# Adafruit_LPS35HW.net
KiCad netlist of a schematic drawn in EAGLE
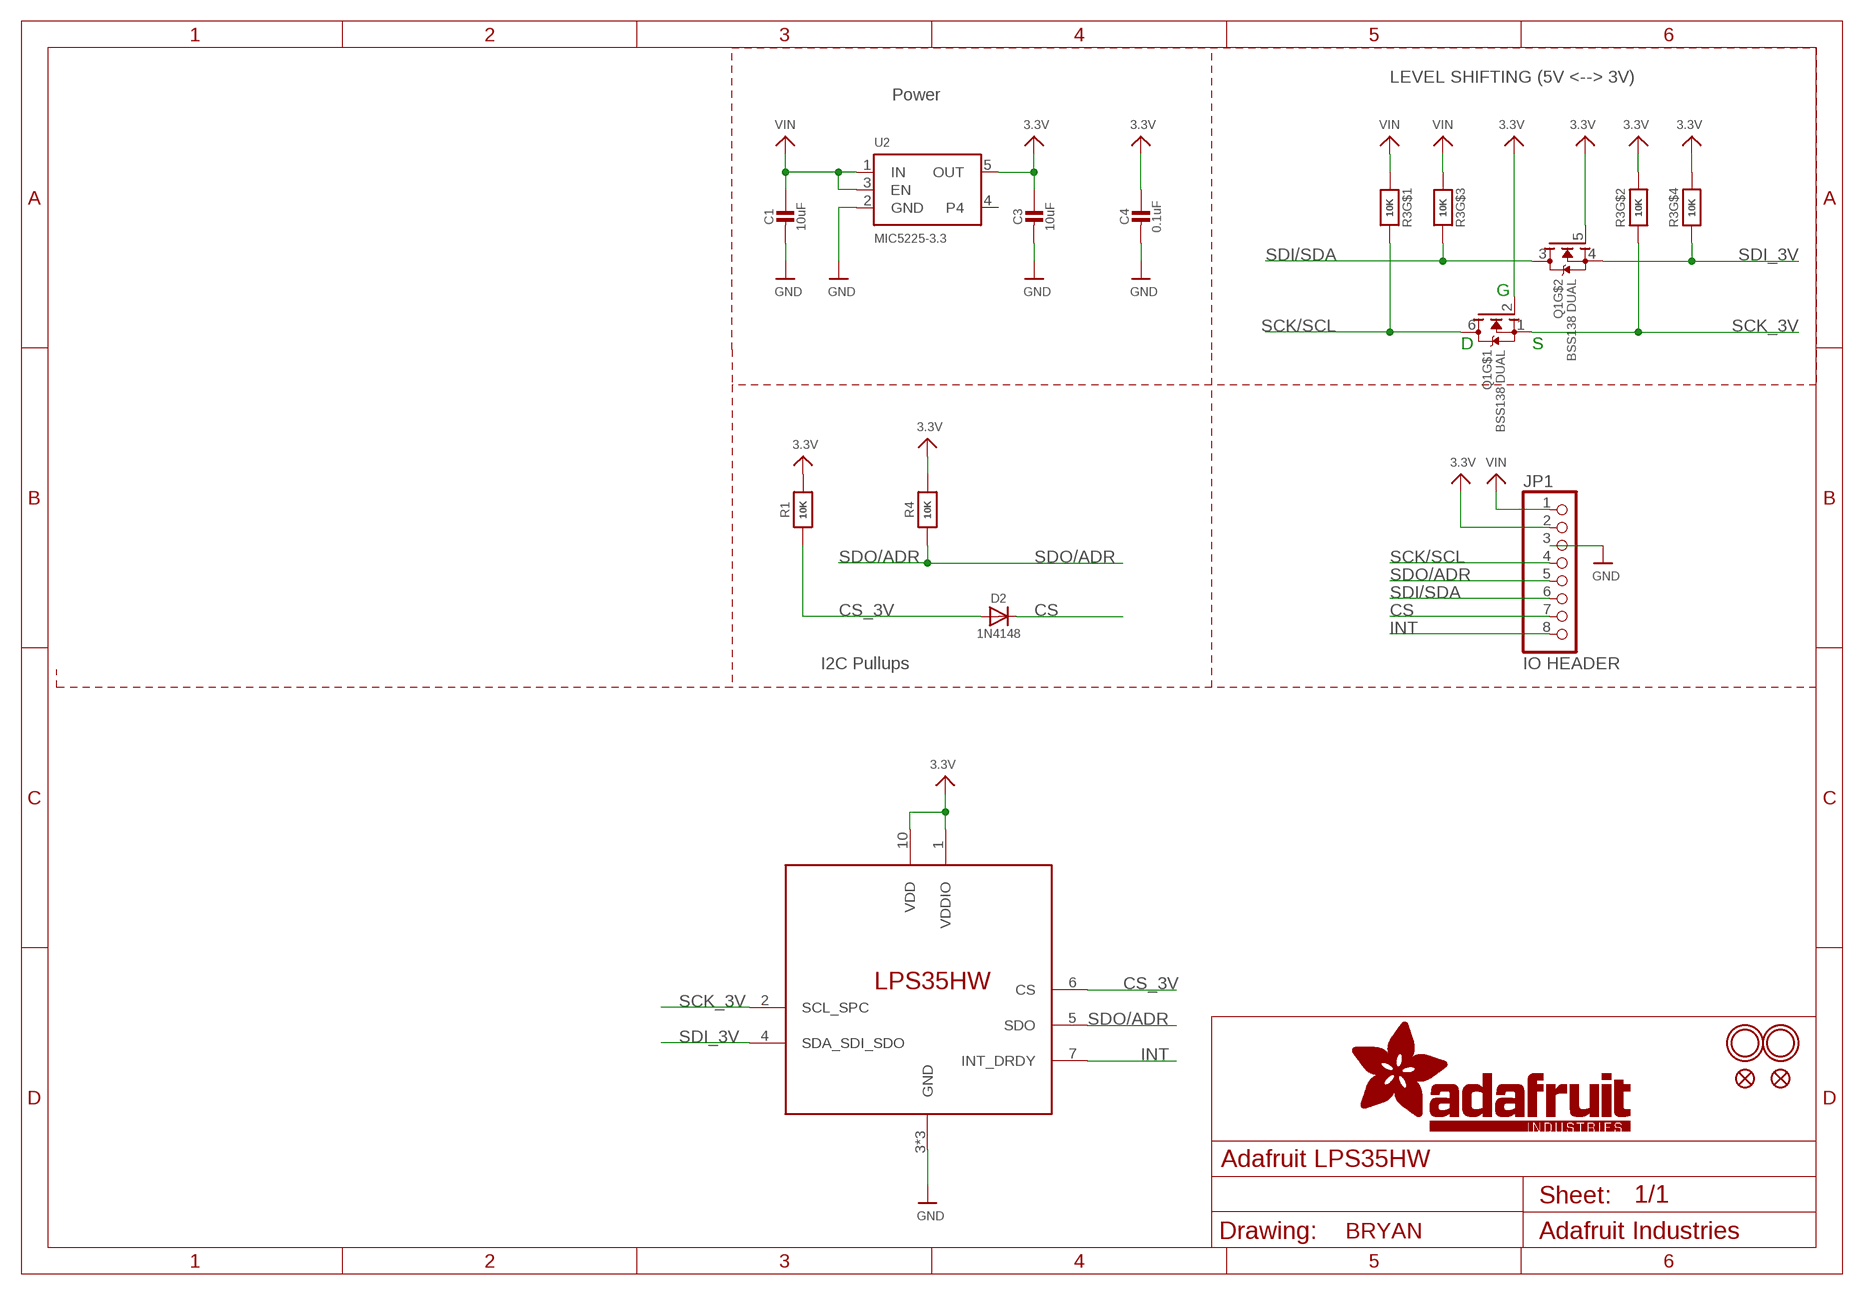
[diagram p0: schematic, sheet 1]

(export (version "E")
  (design (tool "Eeschema 10.0.6"))
  (components
    (comp (ref "C1")
      (value "10uF")
      (footprint "eagle-import:0805-NO")
      (libsource (lib "eagle-import") (part "CAP_CERAMIC0805-NOOUTLINE"))
    )
    (comp (ref "C3")
      (value "10uF")
      (footprint "eagle-import:0805-NO")
      (libsource (lib "eagle-import") (part "CAP_CERAMIC0805-NOOUTLINE"))
    )
    (comp (ref "C4")
      (value "0.1uF")
      (footprint "eagle-import:0603-NO")
      (libsource (lib "eagle-import") (part "CAP_CERAMIC0603_NO"))
    )
    (comp (ref "D2")
      (value "1N4148")
      (footprint "eagle-import:SOD-323")
      (libsource (lib "eagle-import") (part "DIODESOD-323"))
    )
    (comp (ref "JP1")
      (value "IO HEADER")
      (footprint "eagle-import:1X08_ROUND")
      (libsource (lib "eagle-import") (part "HEADER-1X8ROUND"))
    )
    (comp (ref "Q1")
      (value "BSS138 DUAL")
      (footprint "eagle-import:SOT363")
      (libsource (lib "eagle-import") (part "MOSFET-N_DUAL"))
    )
    (comp (ref "R1")
      (value "10K")
      (footprint "eagle-import:0603-NO")
      (libsource (lib "eagle-import") (part "RESISTOR_0603_NOOUT"))
    )
    (comp (ref "R3")
      (value "10K")
      (footprint "eagle-import:RESPACK_4X0603")
      (libsource (lib "eagle-import") (part "RESISTOR_4PACK"))
    )
    (comp (ref "R4")
      (value "10K")
      (footprint "eagle-import:0603-NO")
      (libsource (lib "eagle-import") (part "RESISTOR_0603_NOOUT"))
    )
    (comp (ref "U$3")
      (value "LPS35HWLPS35HW")
      (footprint "eagle-import:CCLGA10L")
      (libsource (lib "eagle-import") (part "LPS35HWLPS35HW"))
    )
    (comp (ref "U$5")
      (value "FIDUCIAL_1MM")
      (footprint "eagle-import:FIDUCIAL_1MM")
      (libsource (lib "eagle-import") (part "FIDUCIAL_1MM"))
    )
    (comp (ref "U$7")
      (value "MOUNTINGHOLE2.0")
      (footprint "eagle-import:MOUNTINGHOLE_2.0_PLATED")
      (libsource (lib "eagle-import") (part "MOUNTINGHOLE2.0"))
    )
    (comp (ref "U$8")
      (value "MOUNTINGHOLE2.0")
      (footprint "eagle-import:MOUNTINGHOLE_2.0_PLATED")
      (libsource (lib "eagle-import") (part "MOUNTINGHOLE2.0"))
    )
    (comp (ref "U$15")
      (value "FIDUCIAL_1MM")
      (footprint "eagle-import:FIDUCIAL_1MM")
      (libsource (lib "eagle-import") (part "FIDUCIAL_1MM"))
    )
    (comp (ref "U2")
      (value "MIC5225-3.3")
      (footprint "eagle-import:SOT23-5")
      (libsource (lib "eagle-import") (part "VREG_SOT23-5"))
    )
  )
  (nets
    (net (code "1") (name "/CS") (class "Default")
      (node (ref "D2") (pin "C") (pinfunction "C_C") (pintype "passive"))
      (node (ref "JP1") (pin "7") (pinfunction "7_7") (pintype "passive"))
    )
    (net (code "2") (name "/CS_3V") (class "Default")
      (node (ref "D2") (pin "A") (pinfunction "A_A") (pintype "passive"))
      (node (ref "R1") (pin "1") (pinfunction "1_1") (pintype "passive"))
      (node (ref "U$3") (pin "6") (pinfunction "CS_6") (pintype "bidirectional"))
    )
    (net (code "3") (name "/INT") (class "Default")
      (node (ref "JP1") (pin "8") (pinfunction "8_8") (pintype "passive"))
      (node (ref "U$3") (pin "7") (pinfunction "INT_DRDY_7") (pintype "output"))
    )
    (net (code "4") (name "/SCK_3V") (class "Default")
      (node (ref "Q1") (pin "1") (pinfunction "S_1") (pintype "bidirectional"))
      (node (ref "R3") (pin "7") (pinfunction "2_7") (pintype "passive"))
      (node (ref "U$3") (pin "2") (pinfunction "SCL_SPC_2") (pintype "input"))
    )
    (net (code "5") (name "/SCK{slash}SCL") (class "Default")
      (node (ref "JP1") (pin "4") (pinfunction "4_4") (pintype "passive"))
      (node (ref "Q1") (pin "6") (pinfunction "D_6") (pintype "bidirectional"))
      (node (ref "R3") (pin "8") (pinfunction "2_8") (pintype "passive"))
    )
    (net (code "6") (name "/SDI_3V") (class "Default")
      (node (ref "Q1") (pin "4") (pinfunction "S_4") (pintype "bidirectional"))
      (node (ref "R3") (pin "5") (pinfunction "2_5") (pintype "passive"))
      (node (ref "U$3") (pin "4") (pinfunction "SDA_SDI_SDO_4") (pintype "bidirectional"))
    )
    (net (code "7") (name "/SDI{slash}SDA") (class "Default")
      (node (ref "JP1") (pin "6") (pinfunction "6_6") (pintype "passive"))
      (node (ref "Q1") (pin "3") (pinfunction "D_3") (pintype "bidirectional"))
      (node (ref "R3") (pin "6") (pinfunction "2_6") (pintype "passive"))
    )
    (net (code "8") (name "/SDO{slash}ADR") (class "Default")
      (node (ref "JP1") (pin "5") (pinfunction "5_5") (pintype "passive"))
      (node (ref "R4") (pin "1") (pinfunction "1_1") (pintype "passive"))
      (node (ref "U$3") (pin "5") (pinfunction "SDO_5") (pintype "bidirectional"))
    )
    (net (code "9") (name "3.3V") (class "Default")
      (node (ref "C3") (pin "1") (pinfunction "1_1") (pintype "passive"))
      (node (ref "C4") (pin "1") (pinfunction "1_1") (pintype "passive"))
      (node (ref "JP1") (pin "2") (pinfunction "2_2") (pintype "passive"))
      (node (ref "Q1") (pin "2") (pinfunction "G_2") (pintype "bidirectional"))
      (node (ref "Q1") (pin "5") (pinfunction "G_5") (pintype "bidirectional"))
      (node (ref "R1") (pin "2") (pinfunction "2_2") (pintype "passive"))
      (node (ref "R3") (pin "2") (pinfunction "1_2") (pintype "passive"))
      (node (ref "R3") (pin "4") (pinfunction "1_4") (pintype "passive"))
      (node (ref "R4") (pin "2") (pinfunction "2_2") (pintype "passive"))
      (node (ref "U$3") (pin "1") (pinfunction "VDDIO_1") (pintype "power_in"))
      (node (ref "U$3") (pin "10") (pinfunction "VDD_10") (pintype "power_in"))
      (node (ref "U2") (pin "5") (pinfunction "OUT_5") (pintype "power_in"))
    )
    (net (code "10") (name "GND") (class "Default")
      (node (ref "C1") (pin "2") (pinfunction "2_2") (pintype "passive"))
      (node (ref "C3") (pin "2") (pinfunction "2_2") (pintype "passive"))
      (node (ref "C4") (pin "2") (pinfunction "2_2") (pintype "passive"))
      (node (ref "JP1") (pin "3") (pinfunction "3_3") (pintype "passive"))
      (node (ref "U$3") (pin "3") (pinfunction "GND_3") (pintype "power_in"))
      (node (ref "U$3") (pin "8") (pinfunction "GND_8") (pintype "power_in"))
      (node (ref "U$3") (pin "9") (pinfunction "GND_9") (pintype "power_in"))
      (node (ref "U2") (pin "2") (pinfunction "GND_2") (pintype "power_in"))
    )
    (net (code "11") (name "VIN") (class "Default")
      (node (ref "C1") (pin "1") (pinfunction "1_1") (pintype "passive"))
      (node (ref "JP1") (pin "1") (pinfunction "1_1") (pintype "passive"))
      (node (ref "R3") (pin "1") (pinfunction "1_1") (pintype "passive"))
      (node (ref "R3") (pin "3") (pinfunction "1_3") (pintype "passive"))
      (node (ref "U2") (pin "1") (pinfunction "IN_1") (pintype "power_in"))
      (node (ref "U2") (pin "3") (pinfunction "EN_3") (pintype "input"))
    )
    (net (code "12") (name "unconnected-(U2-P4-Pad4)") (class "Default")
      (node (ref "U2") (pin "4") (pinfunction "P4_4") (pintype "bidirectional"))
    )
  )
)
